# USB_Circuit.net
KiCad netlist of a schematic drawn in EAGLE
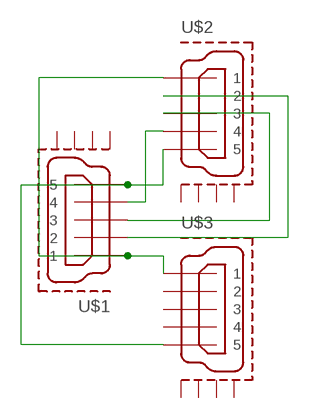
[diagram p0: schematic, sheet 1]

(export (version "E")
  (design (tool "Eeschema 10.0.6"))
  (components
    (comp (ref "U$1")
      (value "MICRO-USB-RECEPTACLE47589-0001")
      (footprint "eagle-import:47589-0001")
      (libsource (lib "eagle-import") (part "MICRO-USB-RECEPTACLE47589-0001"))
    )
    (comp (ref "U$2")
      (value "MICRO-USB-RECEPTACLE47589-0001")
      (footprint "eagle-import:47589-0001")
      (libsource (lib "eagle-import") (part "MICRO-USB-RECEPTACLE47589-0001"))
    )
    (comp (ref "U$3")
      (value "MICRO-USB-RECEPTACLE47589-0001")
      (footprint "eagle-import:47589-0001")
      (libsource (lib "eagle-import") (part "MICRO-USB-RECEPTACLE47589-0001"))
    )
  )
  (nets
    (net (code "1") (name "Net-(U$1-Pad1)") (class "Default")
      (node (ref "U$1") (pin "1") (pinfunction "1_1") (pintype "input"))
      (node (ref "U$2") (pin "1") (pinfunction "1_1") (pintype "input"))
      (node (ref "U$3") (pin "1") (pinfunction "1_1") (pintype "input"))
    )
    (net (code "2") (name "Net-(U$1-Pad2)") (class "Default")
      (node (ref "U$1") (pin "2") (pinfunction "2_2") (pintype "input"))
      (node (ref "U$2") (pin "2") (pinfunction "2_2") (pintype "input"))
    )
    (net (code "3") (name "Net-(U$1-Pad3)") (class "Default")
      (node (ref "U$1") (pin "3") (pinfunction "3_3") (pintype "input"))
      (node (ref "U$2") (pin "3") (pinfunction "3_3") (pintype "input"))
    )
    (net (code "4") (name "Net-(U$1-Pad4)") (class "Default")
      (node (ref "U$1") (pin "4") (pinfunction "4_4") (pintype "input"))
      (node (ref "U$2") (pin "4") (pinfunction "4_4") (pintype "input"))
    )
    (net (code "5") (name "Net-(U$1-Pad5)") (class "Default")
      (node (ref "U$1") (pin "5") (pinfunction "5_5") (pintype "input"))
      (node (ref "U$2") (pin "5") (pinfunction "5_5") (pintype "input"))
      (node (ref "U$3") (pin "5") (pinfunction "5_5") (pintype "input"))
    )
    (net (code "6") (name "unconnected-(U$1-GND1-PadCASING1)") (class "Default")
      (node (ref "U$1") (pin "CASING1") (pinfunction "GND1_CASING1") (pintype "bidirectional"))
    )
    (net (code "7") (name "unconnected-(U$1-GND2-PadCASING2)") (class "Default")
      (node (ref "U$1") (pin "CASING2") (pinfunction "GND2_CASING2") (pintype "bidirectional"))
    )
    (net (code "8") (name "unconnected-(U$1-GND3-PadCASING3)") (class "Default")
      (node (ref "U$1") (pin "CASING3") (pinfunction "GND3_CASING3") (pintype "bidirectional"))
    )
    (net (code "9") (name "unconnected-(U$1-GND4-PadCASING4)") (class "Default")
      (node (ref "U$1") (pin "CASING4") (pinfunction "GND4_CASING4") (pintype "bidirectional"))
    )
    (net (code "10") (name "unconnected-(U$2-GND1-PadCASING1)") (class "Default")
      (node (ref "U$2") (pin "CASING1") (pinfunction "GND1_CASING1") (pintype "bidirectional"))
    )
    (net (code "11") (name "unconnected-(U$2-GND2-PadCASING2)") (class "Default")
      (node (ref "U$2") (pin "CASING2") (pinfunction "GND2_CASING2") (pintype "bidirectional"))
    )
    (net (code "12") (name "unconnected-(U$2-GND3-PadCASING3)") (class "Default")
      (node (ref "U$2") (pin "CASING3") (pinfunction "GND3_CASING3") (pintype "bidirectional"))
    )
    (net (code "13") (name "unconnected-(U$2-GND4-PadCASING4)") (class "Default")
      (node (ref "U$2") (pin "CASING4") (pinfunction "GND4_CASING4") (pintype "bidirectional"))
    )
    (net (code "14") (name "unconnected-(U$3-GND1-PadCASING1)") (class "Default")
      (node (ref "U$3") (pin "CASING1") (pinfunction "GND1_CASING1") (pintype "bidirectional"))
    )
    (net (code "15") (name "unconnected-(U$3-GND2-PadCASING2)") (class "Default")
      (node (ref "U$3") (pin "CASING2") (pinfunction "GND2_CASING2") (pintype "bidirectional"))
    )
    (net (code "16") (name "unconnected-(U$3-GND3-PadCASING3)") (class "Default")
      (node (ref "U$3") (pin "CASING3") (pinfunction "GND3_CASING3") (pintype "bidirectional"))
    )
    (net (code "17") (name "unconnected-(U$3-GND4-PadCASING4)") (class "Default")
      (node (ref "U$3") (pin "CASING4") (pinfunction "GND4_CASING4") (pintype "bidirectional"))
    )
    (net (code "18") (name "unconnected-(U$3-Pad2)") (class "Default")
      (node (ref "U$3") (pin "2") (pinfunction "2_2") (pintype "input"))
    )
    (net (code "19") (name "unconnected-(U$3-Pad3)") (class "Default")
      (node (ref "U$3") (pin "3") (pinfunction "3_3") (pintype "input"))
    )
    (net (code "20") (name "unconnected-(U$3-Pad4)") (class "Default")
      (node (ref "U$3") (pin "4") (pinfunction "4_4") (pintype "input"))
    )
  )
)
